# Force_Plate_Power_Supply.net
KiCad netlist of a schematic drawn in Altium Designer
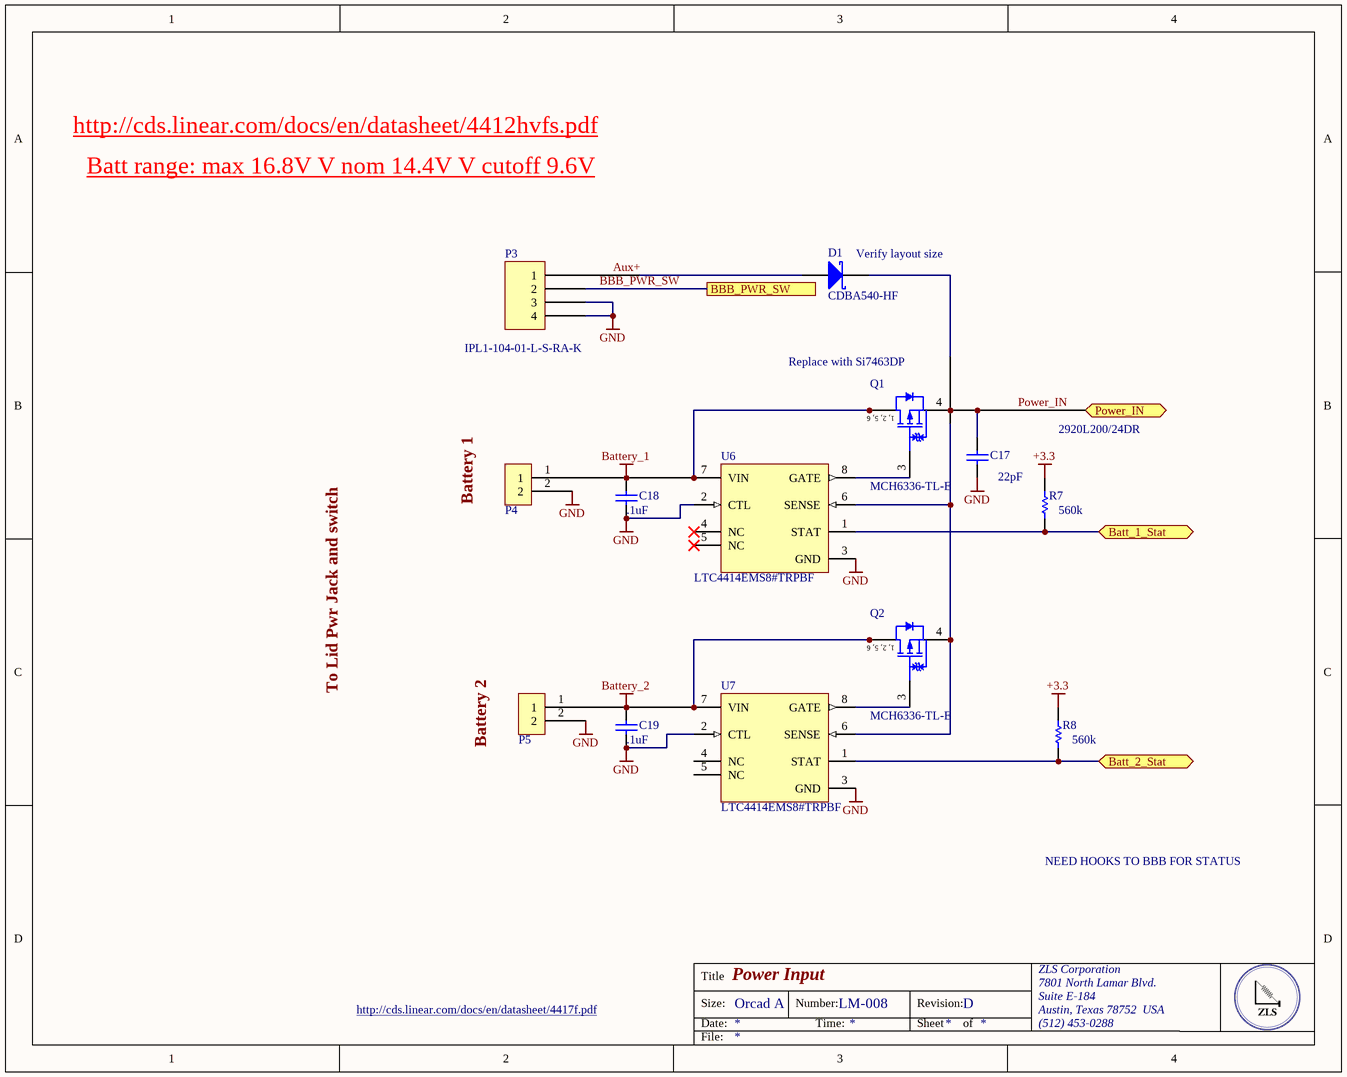
[diagram p0: Force_Plate_Power_Supply.SchDoc]

(export (version "E")
  (design (tool "Eeschema 10.0.6"))
  (components
    (comp (ref "C17")
      (value "CAP CER 10UF 6.3V X5R 1206")
      (footprint "CAPC1206(3216)130_N")
      (fields
        (field (name "MANUFACTURER") "Taiyo Yuden")
        (field (name "MANUFACTURER PART NUMBER") "JMK316BJ106ML-T")
        (field (name "TOLERANCE") "±20%")
        (field (name "CAPACITANCE") "22pF")
      )
      (libsource (lib "Altium Content Vault") (part "CMP-1037-04913-1"))
    )
    (comp (ref "C18")
      (value "CAP CER 10UF 6.3V X5R 1206")
      (footprint "CAPC1206(3216)130_N")
      (fields
        (field (name "MANUFACTURER") "Taiyo Yuden")
        (field (name "MANUFACTURER PART NUMBER") "JMK316BJ106ML-T")
        (field (name "TOLERANCE") "±20%")
        (field (name "CAPACITANCE") ".1uF")
      )
      (libsource (lib "Altium Content Vault") (part "CMP-1037-04913-1"))
    )
    (comp (ref "C19")
      (value "CAP CER 10UF 6.3V X5R 1206")
      (footprint "CAPC1206(3216)130_N")
      (fields
        (field (name "MANUFACTURER") "Taiyo Yuden")
        (field (name "MANUFACTURER PART NUMBER") "JMK316BJ106ML-T")
        (field (name "TOLERANCE") "±20%")
        (field (name "CAPACITANCE") ".1uF")
      )
      (libsource (lib "Altium Content Vault") (part "CMP-1037-04913-1"))
    )
    (comp (ref "D1")
      (value "CDBA540-HF")
      (footprint "VISH-DO-214AC-2_M")
      (description "DIODE SCHOTTKY 40V 5A DO214AB")
      (fields (field (name "MANUFACTURER") "Comchip Technology"))
      (libsource (lib "Miscellaneous Devices") (part "D Schottky"))
    )
    (comp (ref "P3")
      (value "IPL1-104-01-L-S-RA-K")
      (footprint "IPL1-104-01-L-S-RA-K")
      (fields
        (field (name "MANUFACTURER") "Samtec Inc.")
        (field (name "MANUFACTURER PART NUMBER") "IPL1-104-01-L-S-RA-K")
      )
      (libsource (lib "ZLS_Schematic_lib") (part "IPL1-104-01-L-S-RA-K"))
    )
    (comp (ref "P4")
      (value "IPL1-102-01-F-S-RA-K")
      (footprint "IPL1-102-01-F-S-RA-K")
      (libsource (lib "ZLS_Schematic_lib") (part "IPL1-102-01-F-S-RA-K"))
    )
    (comp (ref "P5")
      (value "IPL1-102-01-F-S-RA-K")
      (footprint "IPL1-102-01-F-S-RA-K")
      (libsource (lib "ZLS_Schematic_lib") (part "IPL1-102-01-F-S-RA-K"))
    )
    (comp (ref "Q1")
      (value "MCH6336-TL-E")
      (footprint "ONSC-MCPH-6_V")
      (description "P-Channel Power MOSFET, -12 V, -5 A, 43 mOhm, Single, 6-Pin MCPH, Pb-Free, Tape and Reel")
      (fields (field (name "MANUFACTURER") "On Semiconductor"))
      (libsource (lib "Altium Content Vault") (part "ONSC-PMOS-6_B"))
    )
    (comp (ref "Q2")
      (value "MCH6336-TL-E")
      (footprint "ONSC-MCPH-6_V")
      (description "P-Channel Power MOSFET, -12 V, -5 A, 43 mOhm, Single, 6-Pin MCPH, Pb-Free, Tape and Reel")
      (fields (field (name "MANUFACTURER") "On Semiconductor"))
      (libsource (lib "Altium Content Vault") (part "ONSC-PMOS-6_B"))
    )
    (comp (ref "R7")
      (value "560k")
      (footprint "RESC0402(1005)_L")
      (fields (field (name "TOLERANCE") "±1%"))
      (libsource (lib "Altium Content Vault") (part "CMP-1011-00927-1"))
    )
    (comp (ref "R8")
      (value "560k")
      (footprint "RESC0402(1005)_L")
      (fields (field (name "TOLERANCE") "±1%"))
      (libsource (lib "Altium Content Vault") (part "CMP-1011-00927-1"))
    )
    (comp (ref "U6")
      (value "LTC4414EMS8#TRPBF")
      (footprint "LT-MS8-8_L")
      (fields (field (name "MANUFACTURER") "Linear Technology"))
      (libsource (lib "Altium Content Vault") (part "CMP-0479-00214-1"))
    )
    (comp (ref "U7")
      (value "LTC4414EMS8#TRPBF")
      (footprint "LT-MS8-8_L")
      (fields (field (name "MANUFACTURER") "Linear Technology"))
      (libsource (lib "Altium Content Vault") (part "CMP-0479-00214-1"))
    )
  )
  (nets
    (net (code "1") (name "+3.3") (class "Default")
      (node (ref "R7") (pin "2") (pinfunction "2_2") (pintype "passive"))
      (node (ref "R8") (pin "2") (pinfunction "2_2") (pintype "passive"))
    )
    (net (code "2") (name "/Aux+") (class "Default")
      (node (ref "D1") (pin "1") (pinfunction "A_1") (pintype "passive"))
      (node (ref "P3") (pin "1") (pinfunction "1_1") (pintype "passive"))
    )
    (net (code "3") (name "/BBB_PWR_SW") (class "Default")
      (node (ref "P3") (pin "2") (pinfunction "2_2") (pintype "passive"))
    )
    (net (code "4") (name "/Batt_1_Stat") (class "Default")
      (node (ref "R7") (pin "1") (pinfunction "1_1") (pintype "passive"))
      (node (ref "U6") (pin "1") (pinfunction "STAT_1") (pintype "open_collector"))
    )
    (net (code "5") (name "/Batt_2_Stat") (class "Default")
      (node (ref "R8") (pin "1") (pinfunction "1_1") (pintype "passive"))
      (node (ref "U7") (pin "1") (pinfunction "STAT_1") (pintype "open_collector"))
    )
    (net (code "6") (name "/Power_IN") (class "Default")
      (node (ref "C17") (pin "2") (pinfunction "2_2") (pintype "passive"))
      (node (ref "D1") (pin "2") (pinfunction "K_2") (pintype "passive"))
      (node (ref "Q1") (pin "4") (pinfunction "S_4") (pintype "passive"))
      (node (ref "Q2") (pin "4") (pinfunction "S_4") (pintype "passive"))
      (node (ref "U6") (pin "6") (pinfunction "SENSE_6") (pintype "input"))
      (node (ref "U7") (pin "6") (pinfunction "SENSE_6") (pintype "input"))
    )
    (net (code "7") (name "Battery_1") (class "Default")
      (node (ref "C18") (pin "2") (pinfunction "2_2") (pintype "passive"))
      (node (ref "P4") (pin "1") (pinfunction "1_1") (pintype "passive"))
      (node (ref "Q1") (pin "1") (pinfunction "D_1") (pintype "passive"))
      (node (ref "Q1") (pin "2") (pinfunction "D_2") (pintype "passive"))
      (node (ref "Q1") (pin "5") (pinfunction "D_5") (pintype "passive"))
      (node (ref "Q1") (pin "6") (pinfunction "D_6") (pintype "passive"))
      (node (ref "U6") (pin "7") (pinfunction "VIN_7") (pintype "power_in"))
    )
    (net (code "8") (name "Battery_2") (class "Default")
      (node (ref "C19") (pin "2") (pinfunction "2_2") (pintype "passive"))
      (node (ref "P5") (pin "1") (pinfunction "1_1") (pintype "passive"))
      (node (ref "Q2") (pin "1") (pinfunction "D_1") (pintype "passive"))
      (node (ref "Q2") (pin "2") (pinfunction "D_2") (pintype "passive"))
      (node (ref "Q2") (pin "5") (pinfunction "D_5") (pintype "passive"))
      (node (ref "Q2") (pin "6") (pinfunction "D_6") (pintype "passive"))
      (node (ref "U7") (pin "7") (pinfunction "VIN_7") (pintype "power_in"))
    )
    (net (code "9") (name "GND") (class "Default")
      (node (ref "C17") (pin "1") (pinfunction "1_1") (pintype "passive"))
      (node (ref "C18") (pin "1") (pinfunction "1_1") (pintype "passive"))
      (node (ref "C19") (pin "1") (pinfunction "1_1") (pintype "passive"))
      (node (ref "P3") (pin "3") (pinfunction "3_3") (pintype "passive"))
      (node (ref "P3") (pin "4") (pinfunction "4_4") (pintype "passive"))
      (node (ref "P4") (pin "2") (pinfunction "2_2") (pintype "passive"))
      (node (ref "P5") (pin "2") (pinfunction "2_2") (pintype "passive"))
      (node (ref "U6") (pin "2") (pinfunction "CTL_2") (pintype "input"))
      (node (ref "U6") (pin "3") (pinfunction "GND_3") (pintype "power_in"))
      (node (ref "U7") (pin "2") (pinfunction "CTL_2") (pintype "input"))
      (node (ref "U7") (pin "3") (pinfunction "GND_3") (pintype "power_in"))
    )
    (net (code "10") (name "Net-(Q1-G)") (class "Default")
      (node (ref "Q1") (pin "3") (pinfunction "G_3") (pintype "passive"))
      (node (ref "U6") (pin "8") (pinfunction "GATE_8") (pintype "output"))
    )
    (net (code "11") (name "Net-(Q2-G)") (class "Default")
      (node (ref "Q2") (pin "3") (pinfunction "G_3") (pintype "passive"))
      (node (ref "U7") (pin "8") (pinfunction "GATE_8") (pintype "output"))
    )
    (net (code "12") (name "unconnected-(U6-NC-Pad4)") (class "Default")
      (node (ref "U6") (pin "4") (pinfunction "NC_4") (pintype "passive+no_connect"))
    )
    (net (code "13") (name "unconnected-(U6-NC-Pad5)") (class "Default")
      (node (ref "U6") (pin "5") (pinfunction "NC_5") (pintype "passive+no_connect"))
    )
    (net (code "14") (name "unconnected-(U7-NC-Pad4)") (class "Default")
      (node (ref "U7") (pin "4") (pinfunction "NC_4") (pintype "passive"))
    )
    (net (code "15") (name "unconnected-(U7-NC-Pad5)") (class "Default")
      (node (ref "U7") (pin "5") (pinfunction "NC_5") (pintype "passive"))
    )
  )
)
